# controller15_3.net
KiCad netlist of a schematic drawn in EAGLE
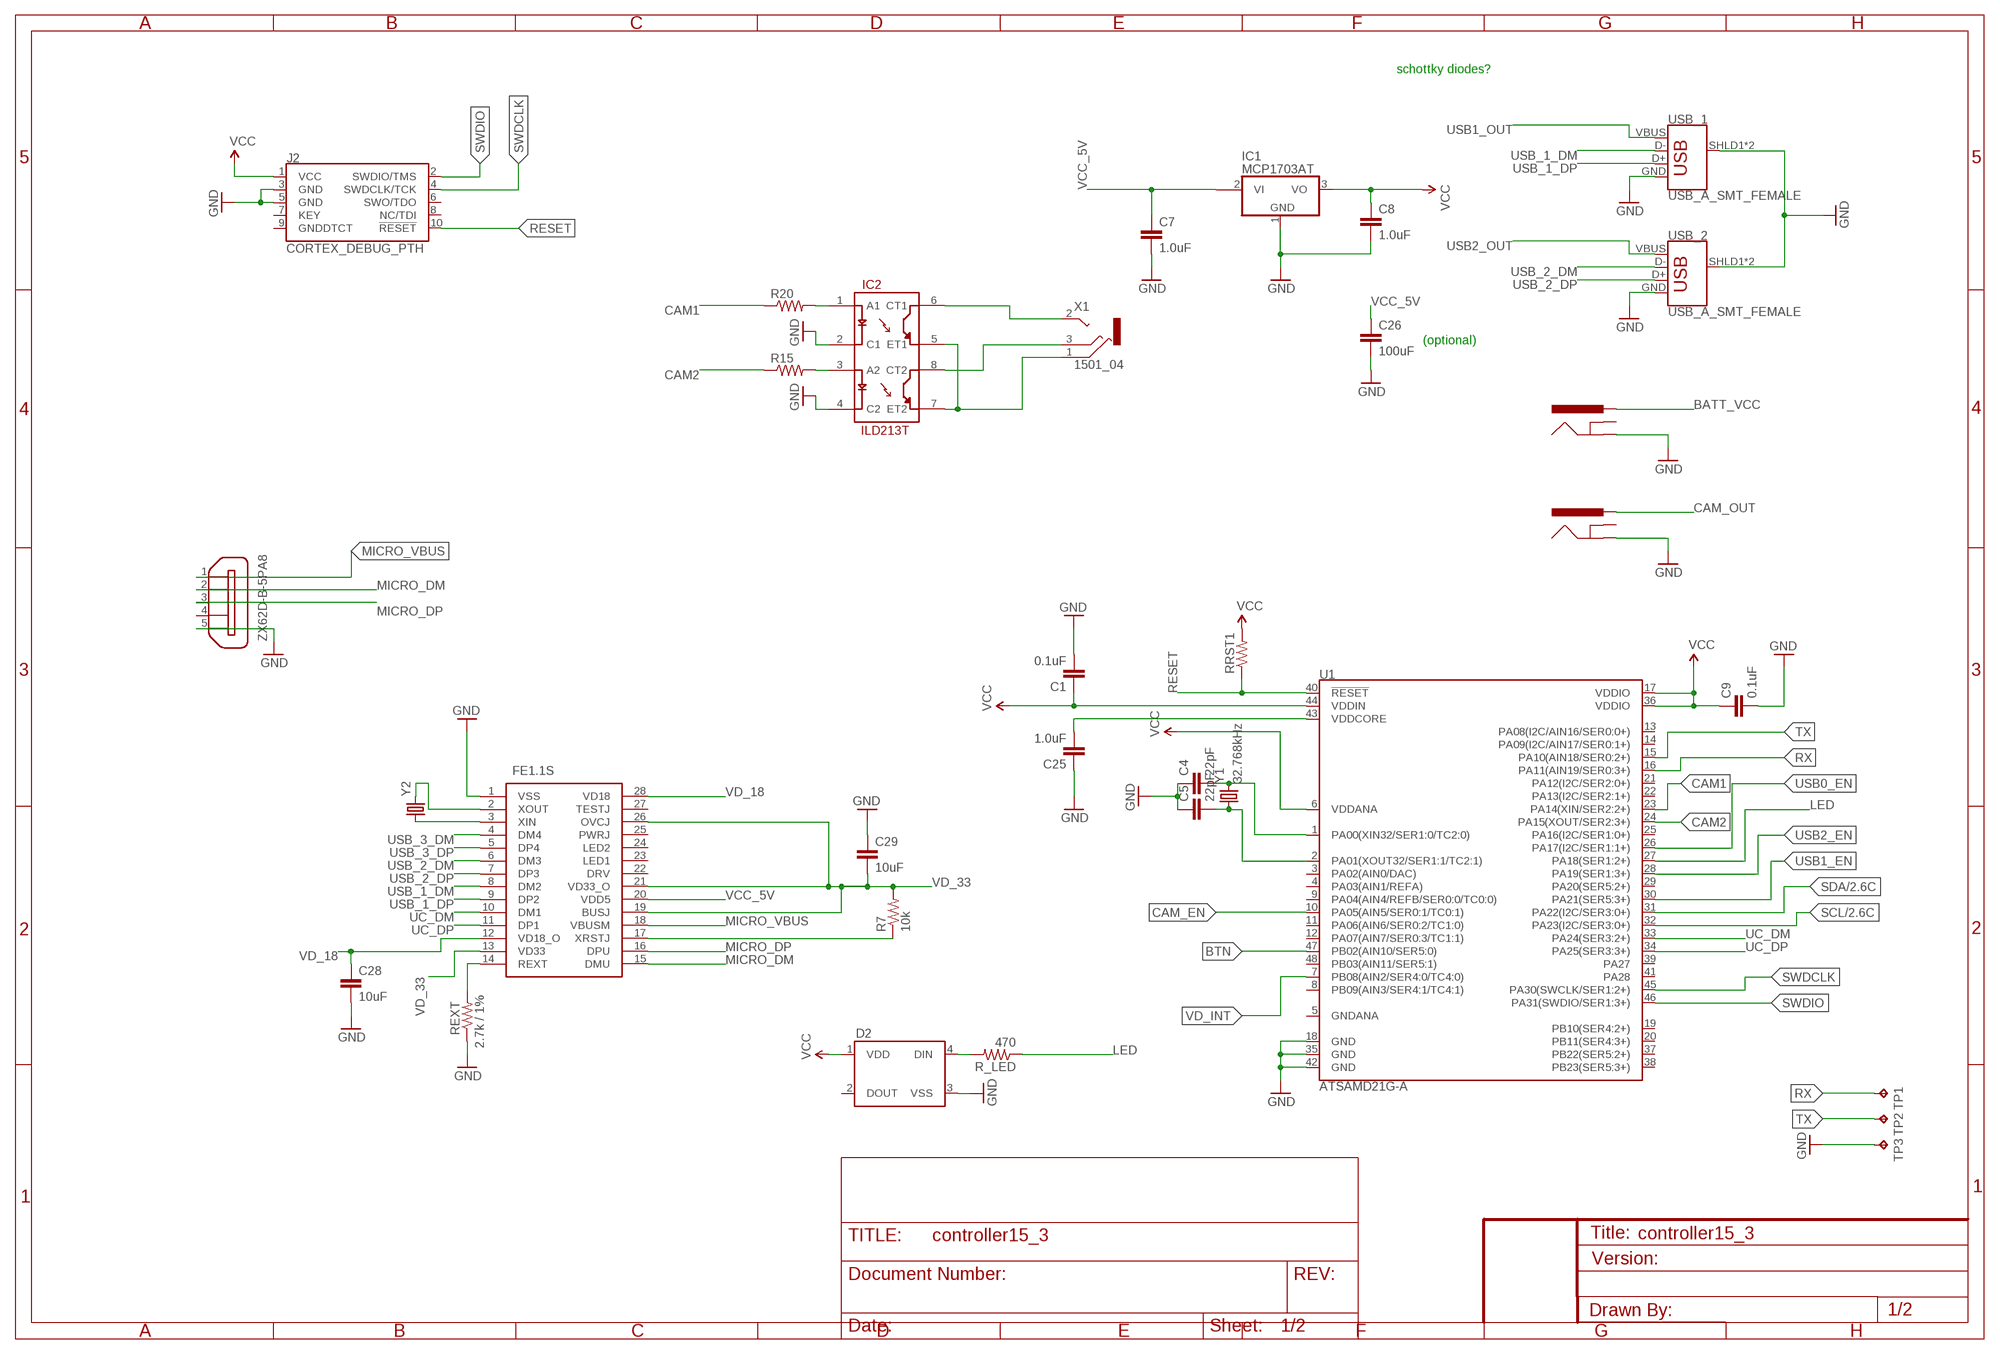
[diagram p0: schematic, sheet 1]
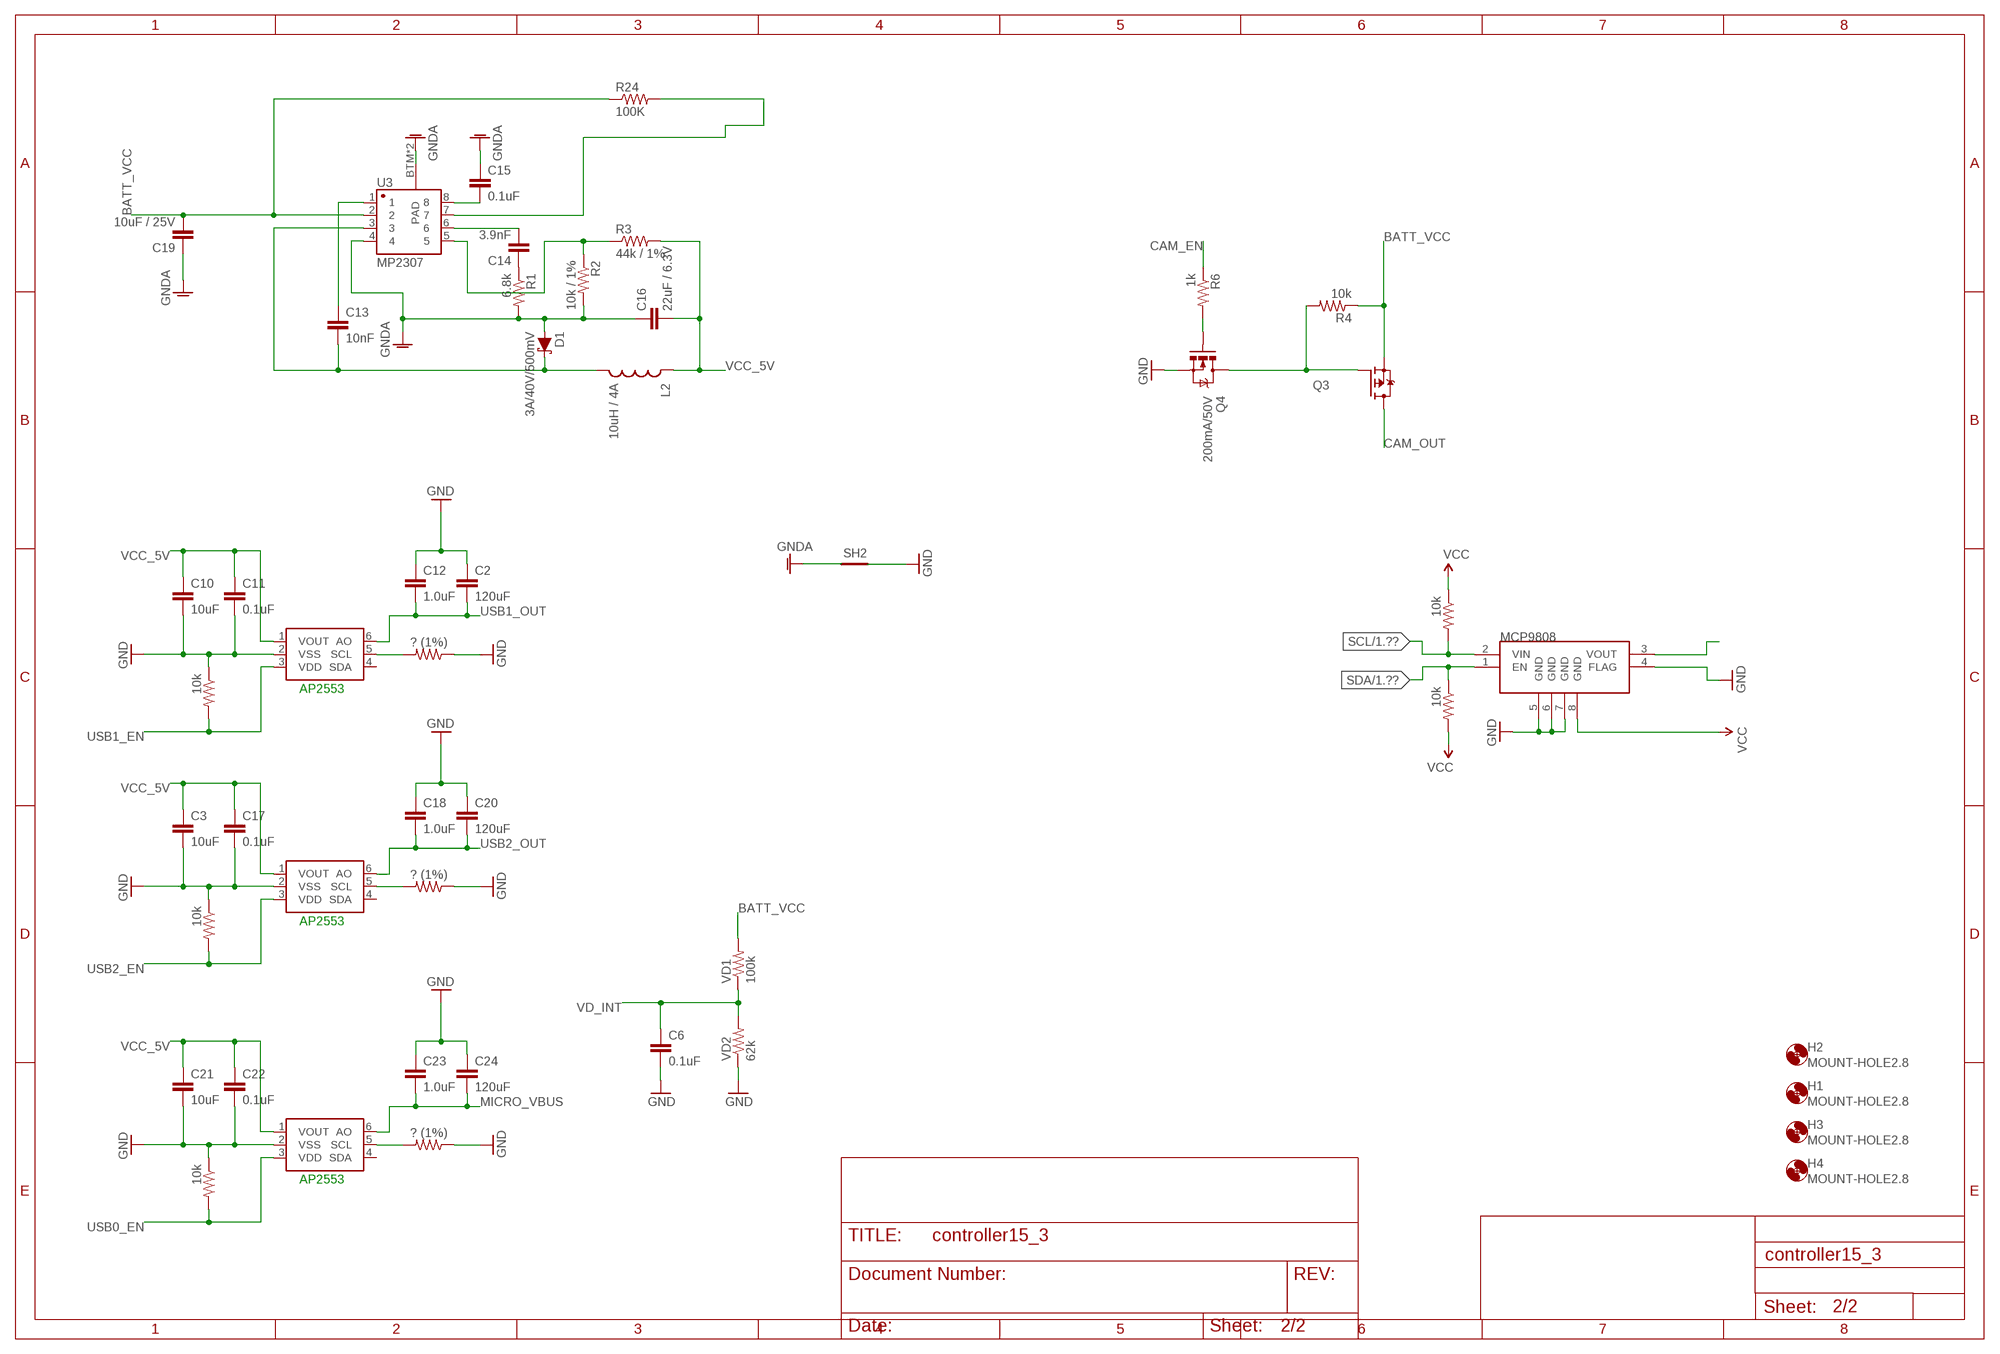
[diagram p1: schematic, sheet 2]

(export (version "E")
  (design (tool "Eeschema 10.0.6"))
  (components
    (comp (ref "AP1")
      (value "MCP4725")
      (footprint "eagle-import:SOT23-6")
      (libsource (lib "eagle-import") (part "MCP4725SOT-23"))
    )
    (comp (ref "AP2")
      (value "MCP4725")
      (footprint "eagle-import:SOT23-6")
      (libsource (lib "eagle-import") (part "MCP4725SOT-23"))
    )
    (comp (ref "AP2553")
      (value "MCP4725")
      (footprint "eagle-import:SOT23-6")
      (libsource (lib "eagle-import") (part "MCP4725SOT-23"))
    )
    (comp (ref "C2")
      (value "120uF")
      (footprint "eagle-import:1206")
      (libsource (lib "eagle-import") (part "1.0UF-1206-50V-10%"))
    )
    (comp (ref "C3")
      (value "10uF")
      (footprint "eagle-import:1206")
      (libsource (lib "eagle-import") (part "1.0UF-1206-50V-10%"))
    )
    (comp (ref "C6")
      (value "0.1uF")
      (footprint "eagle-import:1206")
      (libsource (lib "eagle-import") (part "CAP1206"))
    )
    (comp (ref "C10")
      (value "10uF")
      (footprint "eagle-import:1206")
      (libsource (lib "eagle-import") (part "1.0UF-1206-50V-10%"))
    )
    (comp (ref "C11")
      (value "0.1uF")
      (footprint "eagle-import:0805")
      (libsource (lib "eagle-import") (part "1.0UF-0805-25V-10%"))
    )
    (comp (ref "C12")
      (value "1.0uF")
      (footprint "eagle-import:1206")
      (libsource (lib "eagle-import") (part "1.0UF-1206-50V-10%"))
    )
    (comp (ref "C13")
      (value "10nF")
      (footprint "eagle-import:1206")
      (libsource (lib "eagle-import") (part "CAP1206"))
    )
    (comp (ref "C14")
      (value "3.9nF")
      (footprint "eagle-import:1206")
      (libsource (lib "eagle-import") (part "CAP1206"))
    )
    (comp (ref "C15")
      (value "0.1uF")
      (footprint "eagle-import:1206")
      (libsource (lib "eagle-import") (part "CAP1206"))
    )
    (comp (ref "C16")
      (value "22uF / 6.3V")
      (footprint "eagle-import:1210")
      (libsource (lib "eagle-import") (part "CAP1210"))
    )
    (comp (ref "C17")
      (value "0.1uF")
      (footprint "eagle-import:0805")
      (libsource (lib "eagle-import") (part "1.0UF-0805-25V-10%"))
    )
    (comp (ref "C18")
      (value "1.0uF")
      (footprint "eagle-import:1206")
      (libsource (lib "eagle-import") (part "1.0UF-1206-50V-10%"))
    )
    (comp (ref "C19")
      (value "10uF / 25V")
      (footprint "eagle-import:1210")
      (libsource (lib "eagle-import") (part "CAP1210"))
    )
    (comp (ref "C20")
      (value "120uF")
      (footprint "eagle-import:1206")
      (libsource (lib "eagle-import") (part "1.0UF-1206-50V-10%"))
    )
    (comp (ref "C21")
      (value "10uF")
      (footprint "eagle-import:1206")
      (libsource (lib "eagle-import") (part "1.0UF-1206-50V-10%"))
    )
    (comp (ref "C22")
      (value "0.1uF")
      (footprint "eagle-import:0805")
      (libsource (lib "eagle-import") (part "1.0UF-0805-25V-10%"))
    )
    (comp (ref "C23")
      (value "1.0uF")
      (footprint "eagle-import:1206")
      (libsource (lib "eagle-import") (part "1.0UF-1206-50V-10%"))
    )
    (comp (ref "C24")
      (value "120uF")
      (footprint "eagle-import:1206")
      (libsource (lib "eagle-import") (part "1.0UF-1206-50V-10%"))
    )
    (comp (ref "D1")
      (value "3A/40V/500mV")
      (footprint "eagle-import:SMA-DIODE")
      (libsource (lib "eagle-import") (part "DIODE-SCHOTTKY-B340A"))
    )
    (comp (ref "H1")
      (value "MOUNT-HOLE2.8")
      (footprint "eagle-import:2,8")
      (libsource (lib "eagle-import") (part "MOUNT-HOLE2.8"))
    )
    (comp (ref "H2")
      (value "MOUNT-HOLE2.8")
      (footprint "eagle-import:2,8")
      (libsource (lib "eagle-import") (part "MOUNT-HOLE2.8"))
    )
    (comp (ref "H3")
      (value "MOUNT-HOLE2.8")
      (footprint "eagle-import:2,8")
      (libsource (lib "eagle-import") (part "MOUNT-HOLE2.8"))
    )
    (comp (ref "H4")
      (value "MOUNT-HOLE2.8")
      (footprint "eagle-import:2,8")
      (libsource (lib "eagle-import") (part "MOUNT-HOLE2.8"))
    )
    (comp (ref "L2")
      (value "10uH / 4A")
      (footprint "eagle-import:SRU1038")
      (libsource (lib "eagle-import") (part "INDUCTORSRU1038"))
    )
    (comp (ref "MCP9808")
      (value "V_REG_MIC5216")
      (footprint "eagle-import:MSOP8")
      (libsource (lib "eagle-import") (part "V_REG_MIC5216"))
    )
    (comp (ref "Q3")
      (value "FDD4141TO252")
      (footprint "eagle-import:TO252")
      (libsource (lib "eagle-import") (part "FDD4141TO252"))
    )
    (comp (ref "Q4")
      (value "200mA/50V")
      (footprint "eagle-import:SOT23-3")
      (libsource (lib "eagle-import") (part "MOSFET-NCHANNELBSS138"))
    )
    (comp (ref "R1")
      (value "6.8k")
      (footprint "eagle-import:1206")
      (libsource (lib "eagle-import") (part "SparkFun-Resistors_RESISTOR1206"))
    )
    (comp (ref "R2")
      (value "10k / 1%")
      (footprint "eagle-import:1206")
      (libsource (lib "eagle-import") (part "SparkFun-Resistors_RESISTOR1206"))
    )
    (comp (ref "R3")
      (value "44k / 1%")
      (footprint "eagle-import:1206")
      (libsource (lib "eagle-import") (part "SparkFun-Resistors_RESISTOR1206"))
    )
    (comp (ref "R4")
      (value "10k")
      (footprint "eagle-import:0805")
      (libsource (lib "eagle-import") (part "SparkFun-Resistors_RESISTOR0805-RES"))
    )
    (comp (ref "R6")
      (value "1k")
      (footprint "eagle-import:0805")
      (libsource (lib "eagle-import") (part "SparkFun-Resistors_RESISTOR0805-RES"))
    )
    (comp (ref "R24")
      (value "100K")
      (footprint "eagle-import:1206")
      (libsource (lib "eagle-import") (part "SparkFun-Resistors_RESISTOR1206"))
    )
    (comp (ref "R_I2C_1")
      (value "10k")
      (footprint "eagle-import:0805")
      (libsource (lib "eagle-import") (part "RESISTOR0805-RES"))
    )
    (comp (ref "R_I2C_2")
      (value "10k")
      (footprint "eagle-import:0805")
      (libsource (lib "eagle-import") (part "RESISTOR0805-RES"))
    )
    (comp (ref "R_MOSFET_USB1")
      (value "? (1%)")
      (footprint "eagle-import:0805")
      (libsource (lib "eagle-import") (part "RESISTOR0805-RES"))
    )
    (comp (ref "R_MOSFET_USB2")
      (value "? (1%)")
      (footprint "eagle-import:0805")
      (libsource (lib "eagle-import") (part "RESISTOR0805-RES"))
    )
    (comp (ref "R_MOSFET_USB3")
      (value "10k")
      (footprint "eagle-import:0805")
      (libsource (lib "eagle-import") (part "RESISTOR0805-RES"))
    )
    (comp (ref "R_MOSFET_USB4")
      (value "10k")
      (footprint "eagle-import:0805")
      (libsource (lib "eagle-import") (part "RESISTOR0805-RES"))
    )
    (comp (ref "R_MOSFET_USB5")
      (value "? (1%)")
      (footprint "eagle-import:0805")
      (libsource (lib "eagle-import") (part "RESISTOR0805-RES"))
    )
    (comp (ref "R_MOSFET_USB6")
      (value "10k")
      (footprint "eagle-import:0805")
      (libsource (lib "eagle-import") (part "RESISTOR0805-RES"))
    )
    (comp (ref "SH2")
      (value "SHORT-HT5")
      (footprint "eagle-import:SHORT_TOP-50")
      (libsource (lib "eagle-import") (part "SHORT-HT5"))
    )
    (comp (ref "U3")
      (value "MP2307")
      (footprint "eagle-import:SO08")
      (libsource (lib "eagle-import") (part "GENERIC-SOIC8MSGEQ7N-FILTER"))
    )
    (comp (ref "VD1")
      (value "100k")
      (footprint "eagle-import:1206")
      (libsource (lib "eagle-import") (part "RESISTOR1206"))
    )
    (comp (ref "VD2")
      (value "62k")
      (footprint "eagle-import:1206")
      (libsource (lib "eagle-import") (part "RESISTOR1206"))
    )
    (comp (ref "C1")
      (value "0.1uF")
      (footprint "eagle-import:0805")
      (libsource (lib "eagle-import") (part "1.0UF-0805-25V-10%"))
    )
    (comp (ref "C4")
      (value "22pF")
      (footprint "eagle-import:0805")
      (libsource (lib "eagle-import") (part "SparkFun-Passives_CAP0805"))
    )
    (comp (ref "C5")
      (value "22pF")
      (footprint "eagle-import:0805")
      (libsource (lib "eagle-import") (part "SparkFun-Passives_CAP0805"))
    )
    (comp (ref "C7")
      (value "1.0uF")
      (footprint "eagle-import:1206")
      (libsource (lib "eagle-import") (part "1.0UF-1206-50V-10%"))
    )
    (comp (ref "C8")
      (value "1.0uF")
      (footprint "eagle-import:1206")
      (libsource (lib "eagle-import") (part "1.0UF-1206-50V-10%"))
    )
    (comp (ref "C9")
      (value "0.1uF")
      (footprint "eagle-import:0805")
      (libsource (lib "eagle-import") (part "1.0UF-0805-25V-10%"))
    )
    (comp (ref "C25")
      (value "1.0uF")
      (footprint "eagle-import:0805")
      (libsource (lib "eagle-import") (part "1.0UF-0805-25V-10%"))
    )
    (comp (ref "C26")
      (value "100uF")
      (footprint "eagle-import:1206")
      (libsource (lib "eagle-import") (part "1.0UF-1206-50V-10%"))
    )
    (comp (ref "C28")
      (value "10uF")
      (footprint "eagle-import:0805")
      (libsource (lib "eagle-import") (part "1.0UF-0805-25V-10%"))
    )
    (comp (ref "C29")
      (value "10uF")
      (footprint "eagle-import:0805")
      (libsource (lib "eagle-import") (part "1.0UF-0805-25V-10%"))
    )
    (comp (ref "D2")
      (value "WS2812B")
      (footprint "eagle-import:WS2812B")
      (libsource (lib "eagle-import") (part "WS2812B"))
    )
    (comp (ref "IC1")
      (value "MCP1703AT")
      (footprint "eagle-import:SOT89")
      (libsource (lib "eagle-import") (part "MCP1703MB12"))
    )
    (comp (ref "IC2")
      (value "ILD213T")
      (footprint "eagle-import:SO08")
      (libsource (lib "eagle-import") (part "ILD213T"))
    )
    (comp (ref "IC3")
      (value "FE1.1S")
      (footprint "eagle-import:SOP64P600X175-28N")
      (libsource (lib "eagle-import") (part "FE1.1S"))
    )
    (comp (ref "J2")
      (value "CORTEX_DEBUG_PTH")
      (footprint "eagle-import:2X5-PTH-1.27MM")
      (libsource (lib "eagle-import") (part "CORTEX_DEBUG_PTH"))
    )
    (comp (ref "J3")
      (value "POWER_JACKPTH_BREAD")
      (footprint "eagle-import:POWER_JACK_PTH_BREAD")
      (libsource (lib "eagle-import") (part "POWER_JACKPTH_BREAD"))
    )
    (comp (ref "J4")
      (value "POWER_JACKPTH_BREAD")
      (footprint "eagle-import:POWER_JACK_PTH_BREAD")
      (libsource (lib "eagle-import") (part "POWER_JACKPTH_BREAD"))
    )
    (comp (ref "R7")
      (value "10k")
      (footprint "eagle-import:0805")
      (libsource (lib "eagle-import") (part "RESISTOR0805-RES"))
    )
    (comp (ref "R15")
      (value "RESISTOR0805-RES")
      (footprint "eagle-import:0805")
      (libsource (lib "eagle-import") (part "RESISTOR0805-RES"))
    )
    (comp (ref "R20")
      (value "RESISTOR0805-RES")
      (footprint "eagle-import:0805")
      (libsource (lib "eagle-import") (part "RESISTOR0805-RES"))
    )
    (comp (ref "REXT")
      (value "2.7k / 1%")
      (footprint "eagle-import:0805")
      (libsource (lib "eagle-import") (part "RESISTOR0805-RES"))
    )
    (comp (ref "RRST1")
      (value "RESISTOR0805-RES")
      (footprint "eagle-import:0805")
      (libsource (lib "eagle-import") (part "RESISTOR0805-RES"))
    )
    (comp (ref "R_LED")
      (value "470")
      (footprint "eagle-import:0805")
      (libsource (lib "eagle-import") (part "SparkFun-Resistors_RESISTOR0805-RES"))
    )
    (comp (ref "TP1")
      (value "TPB2,54")
      (footprint "eagle-import:B2,54")
      (libsource (lib "eagle-import") (part "TPB2,54"))
    )
    (comp (ref "TP2")
      (value "TPB2,54")
      (footprint "eagle-import:B2,54")
      (libsource (lib "eagle-import") (part "TPB2,54"))
    )
    (comp (ref "TP3")
      (value "TPB2,54")
      (footprint "eagle-import:B2,54")
      (libsource (lib "eagle-import") (part "TPB2,54"))
    )
    (comp (ref "U1")
      (value "ATSAMD21G-A")
      (footprint "eagle-import:TQFP-48")
      (libsource (lib "eagle-import") (part "ATSAMD21G-A"))
    )
    (comp (ref "USB_1")
      (value "USB_A_SMT_FEMALE")
      (footprint "eagle-import:USB-A-S-SILK-FEMALE")
      (libsource (lib "eagle-import") (part "USB_A_SMT_FEMALE"))
    )
    (comp (ref "USB_2")
      (value "USB_A_SMT_FEMALE")
      (footprint "eagle-import:USB-A-S-SILK-FEMALE")
      (libsource (lib "eagle-import") (part "USB_A_SMT_FEMALE"))
    )
    (comp (ref "X1")
      (value "1501_04")
      (footprint "eagle-import:1501_05")
      (libsource (lib "eagle-import") (part "1501_04"))
    )
    (comp (ref "X2")
      (value "ZX62D-B-5PA8")
      (footprint "eagle-import:ZX62D-B-5PA8")
      (fields (field (name "MF") "Hirose"))
      (libsource (lib "eagle-import") (part "ZX62D-B-5PA8"))
    )
    (comp (ref "Y1")
      (value "32.768kHz")
      (footprint "eagle-import:CRYSTAL-SMD-3.2X1.5MM")
      (libsource (lib "eagle-import") (part "CRYSTAL3.2X1.5MM"))
    )
    (comp (ref "Y2")
      (value "12MHz")
      (footprint "eagle-import:CRYSTAL-SMD-5X3")
      (libsource (lib "eagle-import") (part "CRYSTALCRYSTAL-SMD-5X3-12MHZ"))
    )
  )
  (nets
    (net (code "1") (name "BATT_VCC") (class "Default")
      (node (ref "C19") (pin "2") (pinfunction "2_2") (pintype "passive"))
      (node (ref "J4") (pin "PWR") (pinfunction "PWR_PWR") (pintype "bidirectional"))
      (node (ref "Q3") (pin "2") (pinfunction "S_2") (pintype "passive"))
      (node (ref "R24") (pin "1") (pinfunction "1_1") (pintype "passive"))
      (node (ref "R4") (pin "1") (pinfunction "1_1") (pintype "passive"))
      (node (ref "U3") (pin "2") (pinfunction "2_2") (pintype "bidirectional"))
      (node (ref "VD1") (pin "2") (pinfunction "2_2") (pintype "passive"))
    )
    (net (code "2") (name "BTN") (class "Default")
      (node (ref "U1") (pin "47") (pinfunction "PB02(AIN10/SER5:0)_47") (pintype "bidirectional"))
    )
    (net (code "3") (name "CAM1") (class "Default")
      (node (ref "R20") (pin "1") (pinfunction "1_1") (pintype "passive"))
      (node (ref "U1") (pin "23") (pinfunction "PA14(XIN/SER2:2+)_23") (pintype "bidirectional"))
    )
    (net (code "4") (name "CAM2") (class "Default")
      (node (ref "R15") (pin "1") (pinfunction "1_1") (pintype "passive"))
      (node (ref "U1") (pin "24") (pinfunction "PA15(XOUT/SER2:3+)_24") (pintype "bidirectional"))
    )
    (net (code "5") (name "CAM_EN") (class "Default")
      (node (ref "R6") (pin "1") (pinfunction "1_1") (pintype "passive"))
      (node (ref "U1") (pin "10") (pinfunction "PA05(AIN5/SER0:1/TC0:1)_10") (pintype "bidirectional"))
    )
    (net (code "6") (name "CAM_OUT") (class "Default")
      (node (ref "J3") (pin "PWR") (pinfunction "PWR_PWR") (pintype "bidirectional"))
      (node (ref "Q3") (pin "3") (pinfunction "D_3") (pintype "passive"))
    )
    (net (code "7") (name "GND") (class "Default")
      (node (ref "AP1") (pin "2") (pinfunction "VSS_2") (pintype "bidirectional"))
      (node (ref "AP2") (pin "2") (pinfunction "VSS_2") (pintype "bidirectional"))
      (node (ref "AP2553") (pin "2") (pinfunction "VSS_2") (pintype "bidirectional"))
      (node (ref "C1") (pin "2") (pinfunction "2_2") (pintype "passive"))
      (node (ref "C10") (pin "2") (pinfunction "2_2") (pintype "passive"))
      (node (ref "C11") (pin "2") (pinfunction "2_2") (pintype "passive"))
      (node (ref "C12") (pin "1") (pinfunction "1_1") (pintype "passive"))
      (node (ref "C17") (pin "2") (pinfunction "2_2") (pintype "passive"))
      (node (ref "C18") (pin "1") (pinfunction "1_1") (pintype "passive"))
      (node (ref "C2") (pin "1") (pinfunction "1_1") (pintype "passive"))
      (node (ref "C20") (pin "1") (pinfunction "1_1") (pintype "passive"))
      (node (ref "C21") (pin "2") (pinfunction "2_2") (pintype "passive"))
      (node (ref "C22") (pin "2") (pinfunction "2_2") (pintype "passive"))
      (node (ref "C23") (pin "1") (pinfunction "1_1") (pintype "passive"))
      (node (ref "C24") (pin "1") (pinfunction "1_1") (pintype "passive"))
      (node (ref "C25") (pin "1") (pinfunction "1_1") (pintype "passive"))
      (node (ref "C26") (pin "2") (pinfunction "2_2") (pintype "passive"))
      (node (ref "C28") (pin "2") (pinfunction "2_2") (pintype "passive"))
      (node (ref "C29") (pin "1") (pinfunction "1_1") (pintype "passive"))
      (node (ref "C3") (pin "2") (pinfunction "2_2") (pintype "passive"))
      (node (ref "C4") (pin "1") (pinfunction "1_1") (pintype "passive"))
      (node (ref "C5") (pin "1") (pinfunction "1_1") (pintype "passive"))
      (node (ref "C6") (pin "2") (pinfunction "2_2") (pintype "passive"))
      (node (ref "C7") (pin "2") (pinfunction "2_2") (pintype "passive"))
      (node (ref "C8") (pin "2") (pinfunction "2_2") (pintype "passive"))
      (node (ref "C9") (pin "2") (pinfunction "2_2") (pintype "passive"))
      (node (ref "D2") (pin "3") (pinfunction "VSS_3") (pintype "power_in"))
      (node (ref "IC1") (pin "1") (pinfunction "GND_1") (pintype "passive"))
      (node (ref "IC2") (pin "2") (pinfunction "C1_2") (pintype "bidirectional"))
      (node (ref "IC2") (pin "4") (pinfunction "C2_4") (pintype "bidirectional"))
      (node (ref "IC3") (pin "1") (pinfunction "VSS_1") (pintype "bidirectional"))
      (node (ref "J2") (pin "3") (pinfunction "GND_3") (pintype "bidirectional"))
      (node (ref "J2") (pin "5") (pinfunction "GND_5") (pintype "bidirectional"))
      (node (ref "J3") (pin "GND") (pinfunction "GND_GND") (pintype "bidirectional"))
      (node (ref "J4") (pin "GND") (pinfunction "GND_GND") (pintype "bidirectional"))
      (node (ref "MCP9808") (pin "4") (pinfunction "FLAG_4") (pintype "bidirectional"))
      (node (ref "MCP9808") (pin "5") (pinfunction "GND_5") (pintype "bidirectional"))
      (node (ref "MCP9808") (pin "6") (pinfunction "GND_6") (pintype "bidirectional"))
      (node (ref "MCP9808") (pin "7") (pinfunction "GND_7") (pintype "bidirectional"))
      (node (ref "Q4") (pin "2") (pinfunction "S_2") (pintype "passive"))
      (node (ref "REXT") (pin "1") (pinfunction "1_1") (pintype "passive"))
      (node (ref "R_MOSFET_USB1") (pin "1") (pinfunction "1_1") (pintype "passive"))
      (node (ref "R_MOSFET_USB2") (pin "1") (pinfunction "1_1") (pintype "passive"))
      (node (ref "R_MOSFET_USB3") (pin "1") (pinfunction "1_1") (pintype "passive"))
      (node (ref "R_MOSFET_USB4") (pin "1") (pinfunction "1_1") (pintype "passive"))
      (node (ref "R_MOSFET_USB5") (pin "1") (pinfunction "1_1") (pintype "passive"))
      (node (ref "R_MOSFET_USB6") (pin "1") (pinfunction "1_1") (pintype "passive"))
      (node (ref "SH2") (pin "2") (pinfunction "P$2_2") (pintype "bidirectional"))
      (node (ref "TP3") (pin "TP") (pinfunction "TP_TP") (pintype "input"))
      (node (ref "U1") (pin "18") (pinfunction "GND_18") (pintype "bidirectional"))
      (node (ref "U1") (pin "35") (pinfunction "GND_35") (pintype "bidirectional"))
      (node (ref "U1") (pin "42") (pinfunction "GND_42") (pintype "bidirectional"))
      (node (ref "USB_1") (pin "GND") (pinfunction "GND_GND") (pintype "power_in"))
      (node (ref "USB_1") (pin "SHLD1") (pinfunction "SHIELD_SHLD1") (pintype "bidirectional"))
      (node (ref "USB_1") (pin "SHLD2") (pinfunction "SHIELD_SHLD2") (pintype "bidirectional"))
      (node (ref "USB_2") (pin "GND") (pinfunction "GND_GND") (pintype "power_in"))
      (node (ref "USB_2") (pin "SHLD1") (pinfunction "SHIELD_SHLD1") (pintype "bidirectional"))
      (node (ref "USB_2") (pin "SHLD2") (pinfunction "SHIELD_SHLD2") (pintype "bidirectional"))
      (node (ref "VD2") (pin "1") (pinfunction "1_1") (pintype "passive"))
      (node (ref "X2") (pin "5") (pinfunction "5_5") (pintype "passive"))
    )
    (net (code "8") (name "GNDA") (class "Default")
      (node (ref "C15") (pin "1") (pinfunction "1_1") (pintype "passive"))
      (node (ref "C16") (pin "1") (pinfunction "1_1") (pintype "passive"))
      (node (ref "C19") (pin "1") (pinfunction "1_1") (pintype "passive"))
      (node (ref "D1") (pin "A") (pinfunction "A_A") (pintype "passive"))
      (node (ref "R1") (pin "2") (pinfunction "2_2") (pintype "passive"))
      (node (ref "R2") (pin "2") (pinfunction "2_2") (pintype "passive"))
      (node (ref "SH2") (pin "1") (pinfunction "P$1_1") (pintype "bidirectional"))
      (node (ref "U3") (pin "4") (pinfunction "4_4") (pintype "bidirectional"))
      (node (ref "U3") (pin "BTM") (pinfunction "PAD_BTM") (pintype "bidirectional"))
      (node (ref "U3") (pin "P$1") (pinfunction "PAD_P$1") (pintype "bidirectional"))
    )
    (net (code "9") (name "LED") (class "Default")
      (node (ref "R_LED") (pin "1") (pinfunction "1_1") (pintype "passive"))
      (node (ref "U1") (pin "27") (pinfunction "PA18(SER1:2+)_27") (pintype "bidirectional"))
    )
    (net (code "10") (name "MICRO_DM") (class "Default")
      (node (ref "IC3") (pin "15") (pinfunction "DMU_15") (pintype "bidirectional"))
      (node (ref "X2") (pin "2") (pinfunction "2_2") (pintype "passive"))
    )
    (net (code "11") (name "MICRO_DP") (class "Default")
      (node (ref "IC3") (pin "16") (pinfunction "DPU_16") (pintype "bidirectional"))
      (node (ref "X2") (pin "3") (pinfunction "3_3") (pintype "passive"))
    )
    (net (code "12") (name "MICRO_VBUS") (class "Default")
      (node (ref "AP2") (pin "6") (pinfunction "AO_6") (pintype "bidirectional"))
      (node (ref "C23") (pin "2") (pinfunction "2_2") (pintype "passive"))
      (node (ref "C24") (pin "2") (pinfunction "2_2") (pintype "passive"))
      (node (ref "IC3") (pin "18") (pinfunction "VBUSM_18") (pintype "bidirectional"))
      (node (ref "X2") (pin "1") (pinfunction "1_1") (pintype "passive"))
    )
    (net (code "13") (name "Net-(AP1-SCL)") (class "Default")
      (node (ref "AP1") (pin "5") (pinfunction "SCL_5") (pintype "bidirectional"))
      (node (ref "R_MOSFET_USB2") (pin "2") (pinfunction "2_2") (pintype "passive"))
    )
    (net (code "14") (name "Net-(AP2-SCL)") (class "Default")
      (node (ref "AP2") (pin "5") (pinfunction "SCL_5") (pintype "bidirectional"))
      (node (ref "R_MOSFET_USB5") (pin "2") (pinfunction "2_2") (pintype "passive"))
    )
    (net (code "15") (name "Net-(AP2553-SCL)") (class "Default")
      (node (ref "AP2553") (pin "5") (pinfunction "SCL_5") (pintype "bidirectional"))
      (node (ref "R_MOSFET_USB1") (pin "2") (pinfunction "2_2") (pintype "passive"))
    )
    (net (code "16") (name "Net-(C13-Pad1)") (class "Default")
      (node (ref "C13") (pin "1") (pinfunction "1_1") (pintype "passive"))
      (node (ref "U3") (pin "1") (pinfunction "1_1") (pintype "bidirectional"))
    )
    (net (code "17") (name "Net-(C13-Pad2)") (class "Default")
      (node (ref "C13") (pin "2") (pinfunction "2_2") (pintype "passive"))
      (node (ref "D1") (pin "C") (pinfunction "C_C") (pintype "passive"))
      (node (ref "L2") (pin "2") (pinfunction "2_2") (pintype "passive"))
      (node (ref "U3") (pin "3") (pinfunction "3_3") (pintype "bidirectional"))
    )
    (net (code "18") (name "Net-(C14-Pad1)") (class "Default")
      (node (ref "C14") (pin "1") (pinfunction "1_1") (pintype "passive"))
      (node (ref "R1") (pin "1") (pinfunction "1_1") (pintype "passive"))
    )
    (net (code "19") (name "Net-(C14-Pad2)") (class "Default")
      (node (ref "C14") (pin "2") (pinfunction "2_2") (pintype "passive"))
      (node (ref "U3") (pin "6") (pinfunction "6_6") (pintype "bidirectional"))
    )
    (net (code "20") (name "Net-(C15-Pad2)") (class "Default")
      (node (ref "C15") (pin "2") (pinfunction "2_2") (pintype "passive"))
      (node (ref "U3") (pin "8") (pinfunction "8_8") (pintype "bidirectional"))
    )
    (net (code "21") (name "Net-(D2-DIN)") (class "Default")
      (node (ref "D2") (pin "4") (pinfunction "DIN_4") (pintype "input"))
      (node (ref "R_LED") (pin "2") (pinfunction "2_2") (pintype "passive"))
    )
    (net (code "22") (name "Net-(IC2-A1)") (class "Default")
      (node (ref "IC2") (pin "1") (pinfunction "A1_1") (pintype "bidirectional"))
      (node (ref "R20") (pin "2") (pinfunction "2_2") (pintype "passive"))
    )
    (net (code "23") (name "Net-(IC2-A2)") (class "Default")
      (node (ref "IC2") (pin "3") (pinfunction "A2_3") (pintype "bidirectional"))
      (node (ref "R15") (pin "2") (pinfunction "2_2") (pintype "passive"))
    )
    (net (code "24") (name "Net-(IC2-CT1)") (class "Default")
      (node (ref "IC2") (pin "6") (pinfunction "CT1_6") (pintype "bidirectional"))
      (node (ref "X1") (pin "2") (pinfunction "2_2") (pintype "passive"))
    )
    (net (code "25") (name "Net-(IC2-CT2)") (class "Default")
      (node (ref "IC2") (pin "8") (pinfunction "CT2_8") (pintype "bidirectional"))
      (node (ref "X1") (pin "3") (pinfunction "3_3") (pintype "passive"))
    )
    (net (code "26") (name "Net-(IC2-ET1)") (class "Default")
      (node (ref "IC2") (pin "5") (pinfunction "ET1_5") (pintype "bidirectional"))
      (node (ref "IC2") (pin "7") (pinfunction "ET2_7") (pintype "bidirectional"))
      (node (ref "X1") (pin "1") (pinfunction "1_1") (pintype "passive"))
    )
    (net (code "27") (name "Net-(IC3-REXT)") (class "Default")
      (node (ref "IC3") (pin "14") (pinfunction "REXT_14") (pintype "bidirectional"))
      (node (ref "REXT") (pin "2") (pinfunction "2_2") (pintype "passive"))
    )
    (net (code "28") (name "Net-(IC3-XIN)") (class "Default")
      (node (ref "IC3") (pin "3") (pinfunction "XIN_3") (pintype "bidirectional"))
      (node (ref "Y2") (pin "1") (pinfunction "1_1") (pintype "passive"))
    )
    (net (code "29") (name "Net-(IC3-XOUT)") (class "Default")
      (node (ref "IC3") (pin "2") (pinfunction "XOUT_2") (pintype "bidirectional"))
      (node (ref "Y2") (pin "3") (pinfunction "2_3") (pintype "passive"))
    )
    (net (code "30") (name "Net-(IC3-XRSTJ)") (class "Default")
      (node (ref "IC3") (pin "17") (pinfunction "XRSTJ_17") (pintype "bidirectional"))
      (node (ref "R7") (pin "1") (pinfunction "1_1") (pintype "passive"))
    )
    (net (code "31") (name "Net-(Q3-G)") (class "Default")
      (node (ref "Q3") (pin "1") (pinfunction "G_1") (pintype "passive"))
      (node (ref "Q4") (pin "3") (pinfunction "D_3") (pintype "passive"))
      (node (ref "R4") (pin "2") (pinfunction "2_2") (pintype "passive"))
    )
    (net (code "32") (name "Net-(Q4-G)") (class "Default")
      (node (ref "Q4") (pin "1") (pinfunction "G_1") (pintype "passive"))
      (node (ref "R6") (pin "2") (pinfunction "2_2") (pintype "passive"))
    )
    (net (code "33") (name "Net-(R2-Pad1)") (class "Default")
      (node (ref "R2") (pin "1") (pinfunction "1_1") (pintype "passive"))
      (node (ref "R3") (pin "1") (pinfunction "1_1") (pintype "passive"))
      (node (ref "U3") (pin "5") (pinfunction "5_5") (pintype "bidirectional"))
    )
    (net (code "34") (name "Net-(R24-Pad2)") (class "Default")
      (node (ref "R24") (pin "2") (pinfunction "2_2") (pintype "passive"))
      (node (ref "U3") (pin "7") (pinfunction "7_7") (pintype "bidirectional"))
    )
    (net (code "35") (name "Net-(U1-PA00(XIN32{slash}SER1:0{slash}TC2:0))") (class "Default")
      (node (ref "C4") (pin "2") (pinfunction "2_2") (pintype "passive"))
      (node (ref "U1") (pin "1") (pinfunction "PA00(XIN32/SER1:0/TC2:0)_1") (pintype "bidirectional"))
      (node (ref "Y1") (pin "P$2") (pinfunction "2_P$2") (pintype "passive"))
    )
    (net (code "36") (name "Net-(U1-PA01(XOUT32{slash}SER1:1{slash}TC2:1))") (class "Default")
      (node (ref "C5") (pin "2") (pinfunction "2_2") (pintype "passive"))
      (node (ref "U1") (pin "2") (pinfunction "PA01(XOUT32/SER1:1/TC2:1)_2") (pintype "bidirectional"))
      (node (ref "Y1") (pin "P$1") (pinfunction "1_P$1") (pintype "passive"))
    )
    (net (code "37") (name "Net-(U1-VDDCORE)") (class "Default")
      (node (ref "C25") (pin "2") (pinfunction "2_2") (pintype "passive"))
      (node (ref "U1") (pin "43") (pinfunction "VDDCORE_43") (pintype "bidirectional"))
    )
    (net (code "38") (name "RESET") (class "Default")
      (node (ref "J2") (pin "10") (pinfunction "~{RESET}_10") (pintype "bidirectional"))
      (node (ref "RRST1") (pin "1") (pinfunction "1_1") (pintype "passive"))
      (node (ref "U1") (pin "40") (pinfunction "~{RESET}_40") (pintype "bidirectional"))
    )
    (net (code "39") (name "RX") (class "Default")
      (node (ref "TP1") (pin "TP") (pinfunction "TP_TP") (pintype "input"))
      (node (ref "U1") (pin "16") (pinfunction "PA11(AIN19/SER0:3+)_16") (pintype "bidirectional"))
    )
    (net (code "40") (name "SCL") (class "Default")
      (node (ref "MCP9808") (pin "2") (pinfunction "VIN_2") (pintype "bidirectional"))
      (node (ref "R_I2C_1") (pin "2") (pinfunction "2_2") (pintype "passive"))
      (node (ref "U1") (pin "32") (pinfunction "PA23(I2C/SER3:0+)_32") (pintype "bidirectional"))
    )
    (net (code "41") (name "SDA") (class "Default")
      (node (ref "MCP9808") (pin "1") (pinfunction "EN_1") (pintype "bidirectional"))
      (node (ref "R_I2C_2") (pin "1") (pinfunction "1_1") (pintype "passive"))
      (node (ref "U1") (pin "31") (pinfunction "PA22(I2C/SER3:0+)_31") (pintype "bidirectional"))
    )
    (net (code "42") (name "SWDCLK") (class "Default")
      (node (ref "J2") (pin "4") (pinfunction "SWDCLK/TCK_4") (pintype "bidirectional"))
      (node (ref "U1") (pin "45") (pinfunction "PA30(SWCLK/SER1:2+)_45") (pintype "bidirectional"))
    )
    (net (code "43") (name "SWDIO") (class "Default")
      (node (ref "J2") (pin "2") (pinfunction "SWDIO/TMS_2") (pintype "bidirectional"))
      (node (ref "U1") (pin "46") (pinfunction "PA31(SWDIO/SER1:3+)_46") (pintype "bidirectional"))
    )
    (net (code "44") (name "TX") (class "Default")
      (node (ref "TP2") (pin "TP") (pinfunction "TP_TP") (pintype "input"))
      (node (ref "U1") (pin "15") (pinfunction "PA10(AIN18/SER0:2+)_15") (pintype "bidirectional"))
    )
    (net (code "45") (name "UC_DM") (class "Default")
      (node (ref "IC3") (pin "10") (pinfunction "DM1_10") (pintype "bidirectional"))
      (node (ref "U1") (pin "33") (pinfunction "PA24(SER3:2+)_33") (pintype "bidirectional"))
    )
    (net (code "46") (name "UC_DP") (class "Default")
      (node (ref "IC3") (pin "11") (pinfunction "DP1_11") (pintype "bidirectional"))
      (node (ref "U1") (pin "34") (pinfunction "PA25(SER3:3+)_34") (pintype "bidirectional"))
    )
    (net (code "47") (name "USB0_EN") (class "Default")
      (node (ref "AP2") (pin "3") (pinfunction "VDD_3") (pintype "bidirectional"))
      (node (ref "R_MOSFET_USB6") (pin "2") (pinfunction "2_2") (pintype "passive"))
      (node (ref "U1") (pin "26") (pinfunction "PA17(I2C/SER1:1+)_26") (pintype "bidirectional"))
    )
    (net (code "48") (name "USB1_EN") (class "Default")
      (node (ref "AP2553") (pin "3") (pinfunction "VDD_3") (pintype "bidirectional"))
      (node (ref "R_MOSFET_USB3") (pin "2") (pinfunction "2_2") (pintype "passive"))
      (node (ref "U1") (pin "30") (pinfunction "PA21(SER5:3+)_30") (pintype "bidirectional"))
    )
    (net (code "49") (name "USB1_OUT") (class "Default")
      (node (ref "AP2553") (pin "6") (pinfunction "AO_6") (pintype "bidirectional"))
      (node (ref "C12") (pin "2") (pinfunction "2_2") (pintype "passive"))
      (node (ref "C2") (pin "2") (pinfunction "2_2") (pintype "passive"))
      (node (ref "USB_1") (pin "VBUS") (pinfunction "VBUS_VBUS") (pintype "power_in"))
    )
    (net (code "50") (name "USB2_EN") (class "Default")
      (node (ref "AP1") (pin "3") (pinfunction "VDD_3") (pintype "bidirectional"))
      (node (ref "R_MOSFET_USB4") (pin "2") (pinfunction "2_2") (pintype "passive"))
      (node (ref "U1") (pin "28") (pinfunction "PA19(SER1:3+)_28") (pintype "bidirectional"))
    )
    (net (code "51") (name "USB2_OUT") (class "Default")
      (node (ref "AP1") (pin "6") (pinfunction "AO_6") (pintype "bidirectional"))
      (node (ref "C18") (pin "2") (pinfunction "2_2") (pintype "passive"))
      (node (ref "C20") (pin "2") (pinfunction "2_2") (pintype "passive"))
      (node (ref "USB_2") (pin "VBUS") (pinfunction "VBUS_VBUS") (pintype "power_in"))
    )
    (net (code "52") (name "USB_1_DM") (class "Default")
      (node (ref "IC3") (pin "8") (pinfunction "DM2_8") (pintype "bidirectional"))
      (node (ref "USB_1") (pin "D-") (pinfunction "D-_D-") (pintype "bidirectional"))
    )
    (net (code "53") (name "USB_1_DP") (class "Default")
      (node (ref "IC3") (pin "9") (pinfunction "DP2_9") (pintype "bidirectional"))
      (node (ref "USB_1") (pin "D+") (pinfunction "D+_D+") (pintype "bidirectional"))
    )
    (net (code "54") (name "USB_2_DM") (class "Default")
      (node (ref "IC3") (pin "6") (pinfunction "DM3_6") (pintype "bidirectional"))
      (node (ref "USB_2") (pin "D-") (pinfunction "D-_D-") (pintype "bidirectional"))
    )
    (net (code "55") (name "USB_2_DP") (class "Default")
      (node (ref "IC3") (pin "7") (pinfunction "DP3_7") (pintype "bidirectional"))
      (node (ref "USB_2") (pin "D+") (pinfunction "D+_D+") (pintype "bidirectional"))
    )
    (net (code "56") (name "USB_3_DM") (class "Default")
      (node (ref "IC3") (pin "4") (pinfunction "DM4_4") (pintype "bidirectional"))
    )
    (net (code "57") (name "USB_3_DP") (class "Default")
      (node (ref "IC3") (pin "5") (pinfunction "DP4_5") (pintype "bidirectional"))
    )
    (net (code "58") (name "VCC") (class "Default")
      (node (ref "C1") (pin "1") (pinfunction "1_1") (pintype "passive"))
      (node (ref "C8") (pin "1") (pinfunction "1_1") (pintype "passive"))
      (node (ref "C9") (pin "1") (pinfunction "1_1") (pintype "passive"))
      (node (ref "D2") (pin "1") (pinfunction "VDD_1") (pintype "power_in"))
      (node (ref "IC1") (pin "3") (pinfunction "VO_3") (pintype "passive"))
      (node (ref "J2") (pin "1") (pinfunction "VCC_1") (pintype "bidirectional"))
      (node (ref "MCP9808") (pin "8") (pinfunction "GND_8") (pintype "bidirectional"))
      (node (ref "RRST1") (pin "2") (pinfunction "2_2") (pintype "passive"))
      (node (ref "R_I2C_1") (pin "1") (pinfunction "1_1") (pintype "passive"))
      (node (ref "R_I2C_2") (pin "2") (pinfunction "2_2") (pintype "passive"))
      (node (ref "U1") (pin "17") (pinfunction "VDDIO_17") (pintype "bidirectional"))
      (node (ref "U1") (pin "36") (pinfunction "VDDIO_36") (pintype "bidirectional"))
      (node (ref "U1") (pin "44") (pinfunction "VDDIN_44") (pintype "bidirectional"))
      (node (ref "U1") (pin "6") (pinfunction "VDDANA_6") (pintype "bidirectional"))
    )
    (net (code "59") (name "VCC_5V") (class "Default")
      (node (ref "AP1") (pin "1") (pinfunction "VOUT_1") (pintype "bidirectional"))
      (node (ref "AP2") (pin "1") (pinfunction "VOUT_1") (pintype "bidirectional"))
      (node (ref "AP2553") (pin "1") (pinfunction "VOUT_1") (pintype "bidirectional"))
      (node (ref "C10") (pin "1") (pinfunction "1_1") (pintype "passive"))
      (node (ref "C11") (pin "1") (pinfunction "1_1") (pintype "passive"))
      (node (ref "C16") (pin "2") (pinfunction "2_2") (pintype "passive"))
      (node (ref "C17") (pin "1") (pinfunction "1_1") (pintype "passive"))
      (node (ref "C21") (pin "1") (pinfunction "1_1") (pintype "passive"))
      (node (ref "C22") (pin "1") (pinfunction "1_1") (pintype "passive"))
      (node (ref "C26") (pin "1") (pinfunction "1_1") (pintype "passive"))
      (node (ref "C3") (pin "1") (pinfunction "1_1") (pintype "passive"))
      (node (ref "C7") (pin "1") (pinfunction "1_1") (pintype "passive"))
      (node (ref "IC1") (pin "2@1") (pinfunction "VI1_2@1") (pintype "input"))
      (node (ref "IC3") (pin "20") (pinfunction "VDD5_20") (pintype "bidirectional"))
      (node (ref "L2") (pin "1") (pinfunction "1_1") (pintype "passive"))
      (node (ref "R3") (pin "2") (pinfunction "2_2") (pintype "passive"))
    )
    (net (code "60") (name "VD_18") (class "Default")
      (node (ref "C28") (pin "1") (pinfunction "1_1") (pintype "passive"))
      (node (ref "IC3") (pin "12") (pinfunction "VD18_O_12") (pintype "bidirectional"))
      (node (ref "IC3") (pin "28") (pinfunction "VD18_28") (pintype "bidirectional"))
    )
    (net (code "61") (name "VD_33") (class "Default")
      (node (ref "C29") (pin "2") (pinfunction "2_2") (pintype "passive"))
      (node (ref "IC3") (pin "13") (pinfunction "VD33_13") (pintype "bidirectional"))
      (node (ref "IC3") (pin "19") (pinfunction "BUSJ_19") (pintype "bidirectional"))
      (node (ref "IC3") (pin "21") (pinfunction "VD33_O_21") (pintype "bidirectional"))
      (node (ref "IC3") (pin "26") (pinfunction "OVCJ_26") (pintype "bidirectional"))
      (node (ref "R7") (pin "2") (pinfunction "2_2") (pintype "passive"))
    )
    (net (code "62") (name "VD_INT") (class "Default")
      (node (ref "C6") (pin "1") (pinfunction "1_1") (pintype "passive"))
      (node (ref "U1") (pin "7") (pinfunction "PB08(AIN2/SER4:0/TC4:0)_7") (pintype "bidirectional"))
      (node (ref "VD1") (pin "1") (pinfunction "1_1") (pintype "passive"))
      (node (ref "VD2") (pin "2") (pinfunction "2_2") (pintype "passive"))
    )
    (net (code "63") (name "unconnected-(AP1-SDA-Pad4)") (class "Default")
      (node (ref "AP1") (pin "4") (pinfunction "SDA_4") (pintype "bidirectional"))
    )
    (net (code "64") (name "unconnected-(AP2-SDA-Pad4)") (class "Default")
      (node (ref "AP2") (pin "4") (pinfunction "SDA_4") (pintype "bidirectional"))
    )
    (net (code "65") (name "unconnected-(AP2553-SDA-Pad4)") (class "Default")
      (node (ref "AP2553") (pin "4") (pinfunction "SDA_4") (pintype "bidirectional"))
    )
    (net (code "66") (name "unconnected-(D2-DOUT-Pad2)") (class "Default")
      (node (ref "D2") (pin "2") (pinfunction "DOUT_2") (pintype "output"))
    )
    (net (code "67") (name "unconnected-(IC1-VI-Pad2)") (class "Default")
      (node (ref "IC1") (pin "2") (pinfunction "VI_2") (pintype "input"))
    )
    (net (code "68") (name "unconnected-(IC3-DRV-Pad22)") (class "Default")
      (node (ref "IC3") (pin "22") (pinfunction "DRV_22") (pintype "bidirectional"))
    )
    (net (code "69") (name "unconnected-(IC3-LED1-Pad23)") (class "Default")
      (node (ref "IC3") (pin "23") (pinfunction "LED1_23") (pintype "bidirectional"))
    )
    (net (code "70") (name "unconnected-(IC3-LED2-Pad24)") (class "Default")
      (node (ref "IC3") (pin "24") (pinfunction "LED2_24") (pintype "bidirectional"))
    )
    (net (code "71") (name "unconnected-(IC3-PWRJ-Pad25)") (class "Default")
      (node (ref "IC3") (pin "25") (pinfunction "PWRJ_25") (pintype "bidirectional"))
    )
    (net (code "72") (name "unconnected-(IC3-TESTJ-Pad27)") (class "Default")
      (node (ref "IC3") (pin "27") (pinfunction "TESTJ_27") (pintype "bidirectional"))
    )
    (net (code "73") (name "unconnected-(J2-GNDDTCT-Pad9)") (class "Default")
      (node (ref "J2") (pin "9") (pinfunction "GNDDTCT_9") (pintype "bidirectional"))
    )
    (net (code "74") (name "unconnected-(J2-KEY-Pad7)") (class "Default")
      (node (ref "J2") (pin "7") (pinfunction "KEY_7") (pintype "bidirectional"))
    )
    (net (code "75") (name "unconnected-(J2-NC{slash}TDI-Pad8)") (class "Default")
      (node (ref "J2") (pin "8") (pinfunction "NC/TDI_8") (pintype "bidirectional"))
    )
    (net (code "76") (name "unconnected-(J2-SWO{slash}TDO-Pad6)") (class "Default")
      (node (ref "J2") (pin "6") (pinfunction "SWO/TDO_6") (pintype "bidirectional"))
    )
    (net (code "77") (name "unconnected-(J3-PadGNDBREAK)") (class "Default")
      (node (ref "J3") (pin "GNDBREAK") (pinfunction "GNDBREAK_GNDBREAK") (pintype "bidirectional"))
    )
    (net (code "78") (name "unconnected-(J4-PadGNDBREAK)") (class "Default")
      (node (ref "J4") (pin "GNDBREAK") (pinfunction "GNDBREAK_GNDBREAK") (pintype "bidirectional"))
    )
    (net (code "79") (name "unconnected-(MCP9808-VOUT-Pad3)") (class "Default")
      (node (ref "MCP9808") (pin "3") (pinfunction "VOUT_3") (pintype "bidirectional"))
    )
    (net (code "80") (name "unconnected-(U1-GNDANA-Pad5)") (class "Default")
      (node (ref "U1") (pin "5") (pinfunction "GNDANA_5") (pintype "bidirectional"))
    )
    (net (code "81") (name "unconnected-(U1-PA02(AIN0{slash}DAC)-Pad3)") (class "Default")
      (node (ref "U1") (pin "3") (pinfunction "PA02(AIN0/DAC)_3") (pintype "bidirectional"))
    )
    (net (code "82") (name "unconnected-(U1-PA03(AIN1{slash}REFA)-Pad4)") (class "Default")
      (node (ref "U1") (pin "4") (pinfunction "PA03(AIN1/REFA)_4") (pintype "bidirectional"))
    )
    (net (code "83") (name "unconnected-(U1-PA04(AIN4{slash}REFB{slash}SER0:0{slash}TC0:0)-Pad9)") (class "Default")
      (node (ref "U1") (pin "9") (pinfunction "PA04(AIN4/REFB/SER0:0/TC0:0)_9") (pintype "bidirectional"))
    )
    (net (code "84") (name "unconnected-(U1-PA06(AIN6{slash}SER0:2{slash}TC1:0)-Pad11)") (class "Default")
      (node (ref "U1") (pin "11") (pinfunction "PA06(AIN6/SER0:2/TC1:0)_11") (pintype "bidirectional"))
    )
    (net (code "85") (name "unconnected-(U1-PA07(AIN7{slash}SER0:3{slash}TC1:1)-Pad12)") (class "Default")
      (node (ref "U1") (pin "12") (pinfunction "PA07(AIN7/SER0:3/TC1:1)_12") (pintype "bidirectional"))
    )
    (net (code "86") (name "unconnected-(U1-PA08(I2C{slash}AIN16{slash}SER0:0+)-Pad13)") (class "Default")
      (node (ref "U1") (pin "13") (pinfunction "PA08(I2C/AIN16/SER0:0+)_13") (pintype "bidirectional"))
    )
    (net (code "87") (name "unconnected-(U1-PA09(I2C{slash}AIN17{slash}SER0:1+)-Pad14)") (class "Default")
      (node (ref "U1") (pin "14") (pinfunction "PA09(I2C/AIN17/SER0:1+)_14") (pintype "bidirectional"))
    )
    (net (code "88") (name "unconnected-(U1-PA12(I2C{slash}SER2:0+)-Pad21)") (class "Default")
      (node (ref "U1") (pin "21") (pinfunction "PA12(I2C/SER2:0+)_21") (pintype "bidirectional"))
    )
    (net (code "89") (name "unconnected-(U1-PA13(I2C{slash}SER2:1+)-Pad22)") (class "Default")
      (node (ref "U1") (pin "22") (pinfunction "PA13(I2C/SER2:1+)_22") (pintype "bidirectional"))
    )
    (net (code "90") (name "unconnected-(U1-PA16(I2C{slash}SER1:0+)-Pad25)") (class "Default")
      (node (ref "U1") (pin "25") (pinfunction "PA16(I2C/SER1:0+)_25") (pintype "bidirectional"))
    )
    (net (code "91") (name "unconnected-(U1-PA20(SER5:2+)-Pad29)") (class "Default")
      (node (ref "U1") (pin "29") (pinfunction "PA20(SER5:2+)_29") (pintype "bidirectional"))
    )
    (net (code "92") (name "unconnected-(U1-PA27-Pad39)") (class "Default")
      (node (ref "U1") (pin "39") (pinfunction "PA27_39") (pintype "bidirectional"))
    )
    (net (code "93") (name "unconnected-(U1-PA28-Pad41)") (class "Default")
      (node (ref "U1") (pin "41") (pinfunction "PA28_41") (pintype "bidirectional"))
    )
    (net (code "94") (name "unconnected-(U1-PB03(AIN11{slash}SER5:1)-Pad48)") (class "Default")
      (node (ref "U1") (pin "48") (pinfunction "PB03(AIN11/SER5:1)_48") (pintype "bidirectional"))
    )
    (net (code "95") (name "unconnected-(U1-PB09(AIN3{slash}SER4:1{slash}TC4:1)-Pad8)") (class "Default")
      (node (ref "U1") (pin "8") (pinfunction "PB09(AIN3/SER4:1/TC4:1)_8") (pintype "bidirectional"))
    )
    (net (code "96") (name "unconnected-(U1-PB10(SER4:2+)-Pad19)") (class "Default")
      (node (ref "U1") (pin "19") (pinfunction "PB10(SER4:2+)_19") (pintype "bidirectional"))
    )
    (net (code "97") (name "unconnected-(U1-PB11(SER4:3+)-Pad20)") (class "Default")
      (node (ref "U1") (pin "20") (pinfunction "PB11(SER4:3+)_20") (pintype "bidirectional"))
    )
    (net (code "98") (name "unconnected-(U1-PB22(SER5:2+)-Pad37)") (class "Default")
      (node (ref "U1") (pin "37") (pinfunction "PB22(SER5:2+)_37") (pintype "bidirectional"))
    )
    (net (code "99") (name "unconnected-(U1-PB23(SER5:3+)-Pad38)") (class "Default")
      (node (ref "U1") (pin "38") (pinfunction "PB23(SER5:3+)_38") (pintype "bidirectional"))
    )
    (net (code "100") (name "unconnected-(X2-Pad4)") (class "Default")
      (node (ref "X2") (pin "4") (pinfunction "4_4") (pintype "passive"))
    )
  )
)
